# power-control.net
KiCad netlist of a schematic drawn in EAGLE
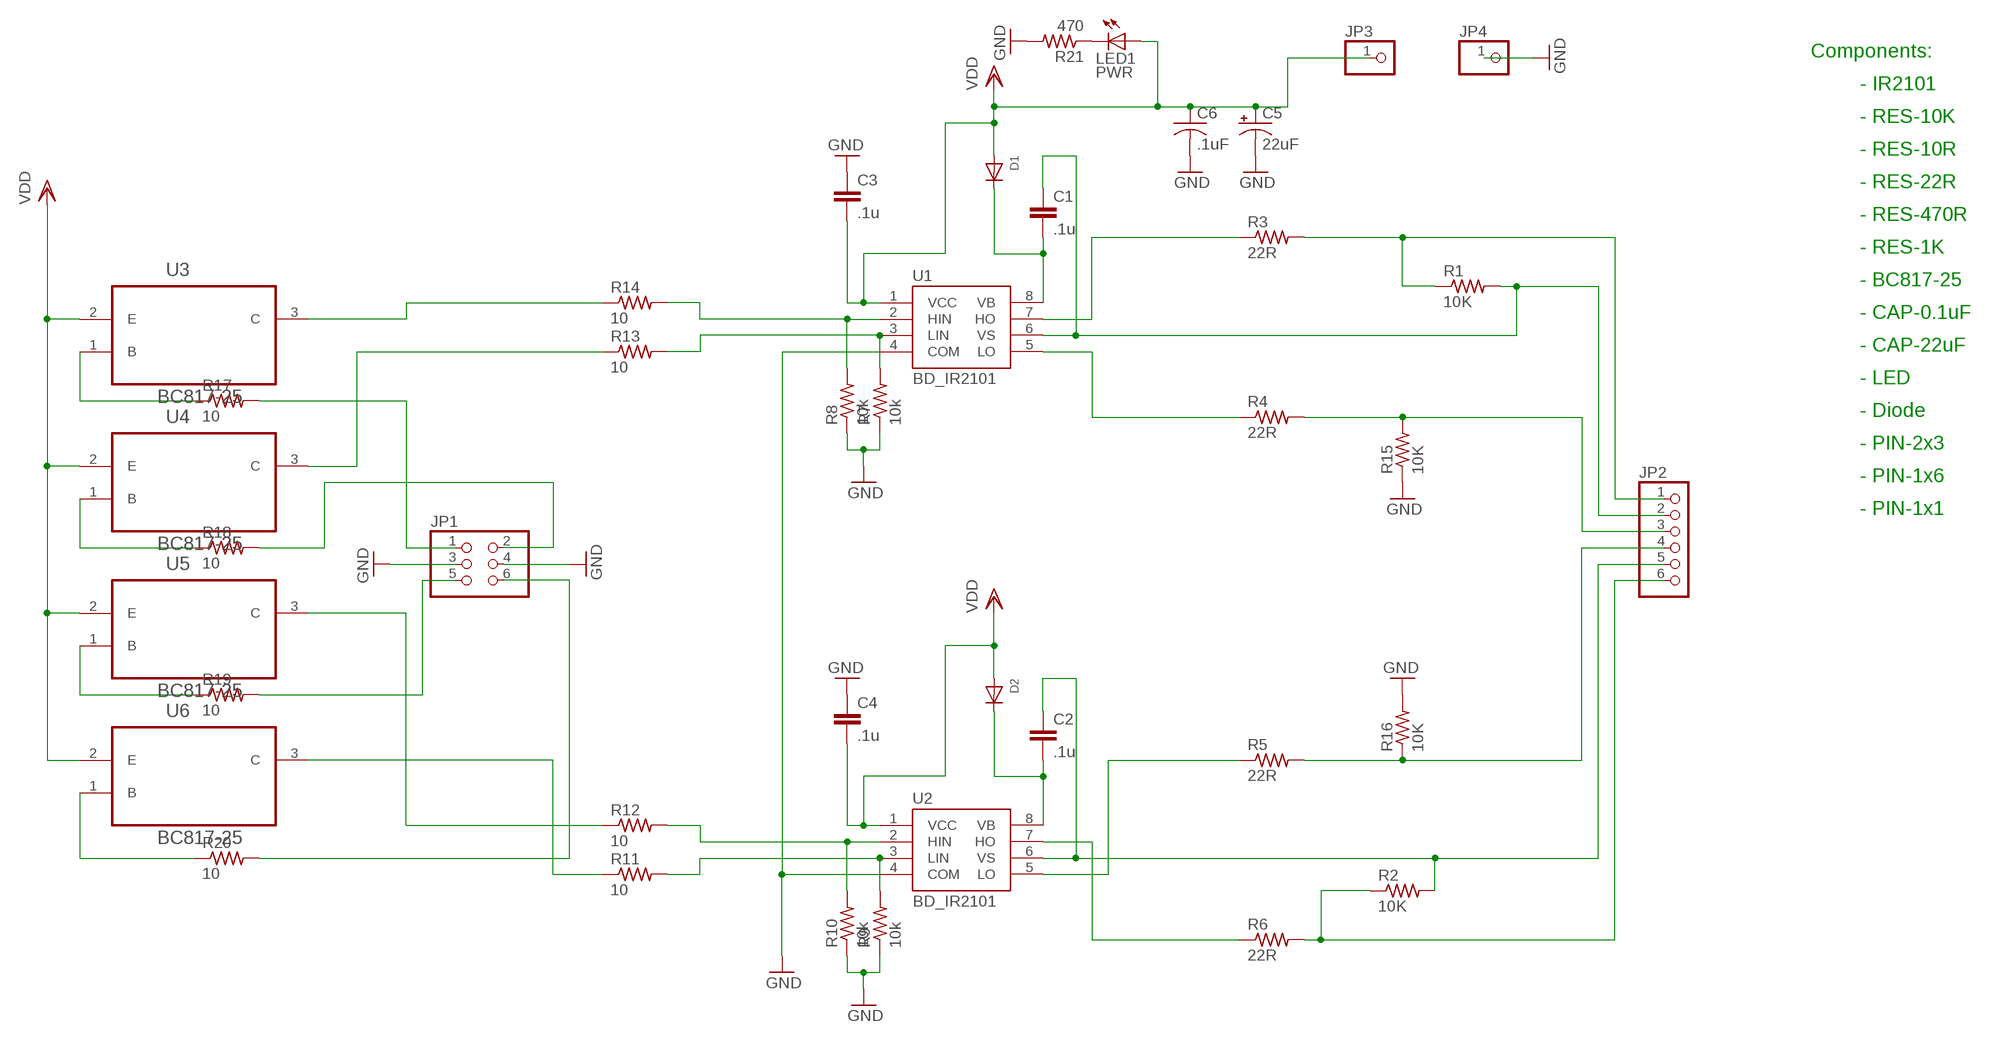
[diagram p0: schematic, sheet 1]

(export (version "E")
  (design (tool "Eeschema 10.0.6"))
  (components
    (comp (ref "C1")
      (value ".1u")
      (footprint "eagle-import:C0603")
      (libsource (lib "eagle-import") (part "C-EUC0603"))
    )
    (comp (ref "C2")
      (value ".1u")
      (footprint "eagle-import:C0603")
      (libsource (lib "eagle-import") (part "C-EUC0603"))
    )
    (comp (ref "C3")
      (value ".1u")
      (footprint "eagle-import:C0603")
      (libsource (lib "eagle-import") (part "C-EUC0603"))
    )
    (comp (ref "C4")
      (value ".1u")
      (footprint "eagle-import:C0603")
      (libsource (lib "eagle-import") (part "C-EUC0603"))
    )
    (comp (ref "C5")
      (value "22uF")
      (footprint "eagle-import:B_3528-21W")
      (libsource (lib "eagle-import") (part "CPOL-USB/3528-21W"))
    )
    (comp (ref "C6")
      (value ".1uF")
      (footprint "eagle-import:C0805")
      (libsource (lib "eagle-import") (part "C-USC0805"))
    )
    (comp (ref "D1")
      (value "DIODESOD-523")
      (footprint "eagle-import:SOD-523")
      (libsource (lib "eagle-import") (part "DIODESOD-523"))
    )
    (comp (ref "D2")
      (value "DIODESOD-523")
      (footprint "eagle-import:SOD-523")
      (libsource (lib "eagle-import") (part "DIODESOD-523"))
    )
    (comp (ref "JP1")
      (value "PINHD-2X3")
      (footprint "eagle-import:2X03")
      (libsource (lib "eagle-import") (part "PINHD-2X3"))
    )
    (comp (ref "JP2")
      (value "PINHD-1X6")
      (footprint "eagle-import:1X06")
      (libsource (lib "eagle-import") (part "PINHD-1X6"))
    )
    (comp (ref "JP3")
      (value "PINHD-1X1")
      (footprint "eagle-import:1X01")
      (libsource (lib "eagle-import") (part "PINHD-1X1"))
    )
    (comp (ref "JP4")
      (value "PINHD-1X1")
      (footprint "eagle-import:1X01")
      (libsource (lib "eagle-import") (part "PINHD-1X1"))
    )
    (comp (ref "LED1")
      (value "PWR")
      (footprint "eagle-import:CHIP-LED0805")
      (libsource (lib "eagle-import") (part "LEDCHIP-LED0805"))
    )
    (comp (ref "R1")
      (value "10K")
      (footprint "eagle-import:R0603")
      (libsource (lib "eagle-import") (part "R-US_R0603"))
    )
    (comp (ref "R2")
      (value "10K")
      (footprint "eagle-import:R0603")
      (libsource (lib "eagle-import") (part "R-US_R0603"))
    )
    (comp (ref "R3")
      (value "22R")
      (footprint "eagle-import:R0603")
      (libsource (lib "eagle-import") (part "R-US_R0603"))
    )
    (comp (ref "R4")
      (value "22R")
      (footprint "eagle-import:R0603")
      (libsource (lib "eagle-import") (part "R-US_R0603"))
    )
    (comp (ref "R5")
      (value "22R")
      (footprint "eagle-import:R0603")
      (libsource (lib "eagle-import") (part "R-US_R0603"))
    )
    (comp (ref "R6")
      (value "22R")
      (footprint "eagle-import:R0603")
      (libsource (lib "eagle-import") (part "R-US_R0603"))
    )
    (comp (ref "R7")
      (value "10k")
      (footprint "eagle-import:R0603")
      (libsource (lib "eagle-import") (part "R-US_R0603"))
    )
    (comp (ref "R8")
      (value "10k")
      (footprint "eagle-import:R0603")
      (libsource (lib "eagle-import") (part "R-US_R0603"))
    )
    (comp (ref "R9")
      (value "10k")
      (footprint "eagle-import:R0603")
      (libsource (lib "eagle-import") (part "R-US_R0603"))
    )
    (comp (ref "R10")
      (value "10k")
      (footprint "eagle-import:R0603")
      (libsource (lib "eagle-import") (part "R-US_R0603"))
    )
    (comp (ref "R11")
      (value "10")
      (footprint "eagle-import:R0603")
      (libsource (lib "eagle-import") (part "R-US_R0603"))
    )
    (comp (ref "R12")
      (value "10")
      (footprint "eagle-import:R0603")
      (libsource (lib "eagle-import") (part "R-US_R0603"))
    )
    (comp (ref "R13")
      (value "10")
      (footprint "eagle-import:R0603")
      (libsource (lib "eagle-import") (part "R-US_R0603"))
    )
    (comp (ref "R14")
      (value "10")
      (footprint "eagle-import:R0603")
      (libsource (lib "eagle-import") (part "R-US_R0603"))
    )
    (comp (ref "R15")
      (value "10K")
      (footprint "eagle-import:R0603")
      (libsource (lib "eagle-import") (part "R-US_R0603"))
    )
    (comp (ref "R16")
      (value "10K")
      (footprint "eagle-import:R0603")
      (libsource (lib "eagle-import") (part "R-US_R0603"))
    )
    (comp (ref "R17")
      (value "10")
      (footprint "eagle-import:R0603")
      (libsource (lib "eagle-import") (part "R-US_R0603"))
    )
    (comp (ref "R18")
      (value "10")
      (footprint "eagle-import:R0603")
      (libsource (lib "eagle-import") (part "R-US_R0603"))
    )
    (comp (ref "R19")
      (value "10")
      (footprint "eagle-import:R0603")
      (libsource (lib "eagle-import") (part "R-US_R0603"))
    )
    (comp (ref "R20")
      (value "10")
      (footprint "eagle-import:R0603")
      (libsource (lib "eagle-import") (part "R-US_R0603"))
    )
    (comp (ref "R21")
      (value "470")
      (footprint "eagle-import:R0603")
      (libsource (lib "eagle-import") (part "R-US_R0603"))
    )
    (comp (ref "U1")
      (value "BD_IR2101")
      (footprint "eagle-import:SO8")
      (libsource (lib "eagle-import") (part "BD_IR2101"))
    )
    (comp (ref "U2")
      (value "BD_IR2101")
      (footprint "eagle-import:SO8")
      (libsource (lib "eagle-import") (part "BD_IR2101"))
    )
    (comp (ref "U3")
      (value "BC817-25")
      (footprint "eagle-import:SOT95P240X97-3N")
      (libsource (lib "eagle-import") (part "BC817-25"))
    )
    (comp (ref "U4")
      (value "BC817-25")
      (footprint "eagle-import:SOT95P240X97-3N")
      (libsource (lib "eagle-import") (part "BC817-25"))
    )
    (comp (ref "U5")
      (value "BC817-25")
      (footprint "eagle-import:SOT95P240X97-3N")
      (libsource (lib "eagle-import") (part "BC817-25"))
    )
    (comp (ref "U6")
      (value "BC817-25")
      (footprint "eagle-import:SOT95P240X97-3N")
      (libsource (lib "eagle-import") (part "BC817-25"))
    )
  )
  (nets
    (net (code "1") (name "GND") (class "Default")
      (node (ref "C3") (pin "1") (pinfunction "1_1") (pintype "passive"))
      (node (ref "C4") (pin "1") (pinfunction "1_1") (pintype "passive"))
      (node (ref "C5") (pin "-") (pinfunction "-_-") (pintype "passive"))
      (node (ref "C6") (pin "2") (pinfunction "2_2") (pintype "passive"))
      (node (ref "JP1") (pin "3") (pinfunction "3_3") (pintype "passive"))
      (node (ref "JP1") (pin "4") (pinfunction "4_4") (pintype "passive"))
      (node (ref "JP4") (pin "1") (pinfunction "1_1") (pintype "passive"))
      (node (ref "R10") (pin "1") (pinfunction "1_1") (pintype "passive"))
      (node (ref "R15") (pin "1") (pinfunction "1_1") (pintype "passive"))
      (node (ref "R16") (pin "2") (pinfunction "2_2") (pintype "passive"))
      (node (ref "R21") (pin "2") (pinfunction "2_2") (pintype "passive"))
      (node (ref "R7") (pin "1") (pinfunction "1_1") (pintype "passive"))
      (node (ref "R8") (pin "1") (pinfunction "1_1") (pintype "passive"))
      (node (ref "R9") (pin "1") (pinfunction "1_1") (pintype "passive"))
      (node (ref "U1") (pin "4") (pinfunction "COM_4") (pintype "bidirectional"))
      (node (ref "U2") (pin "4") (pinfunction "COM_4") (pintype "bidirectional"))
    )
    (net (code "2") (name "Net-(D1-C)") (class "Default")
      (node (ref "C1") (pin "2") (pinfunction "2_2") (pintype "passive"))
      (node (ref "D1") (pin "K") (pinfunction "C_K") (pintype "passive"))
      (node (ref "U1") (pin "8") (pinfunction "VB_8") (pintype "bidirectional"))
    )
    (net (code "3") (name "Net-(D2-C)") (class "Default")
      (node (ref "C2") (pin "2") (pinfunction "2_2") (pintype "passive"))
      (node (ref "D2") (pin "K") (pinfunction "C_K") (pintype "passive"))
      (node (ref "U2") (pin "8") (pinfunction "VB_8") (pintype "bidirectional"))
    )
    (net (code "4") (name "Net-(JP1-Pad1)") (class "Default")
      (node (ref "JP1") (pin "1") (pinfunction "1_1") (pintype "passive"))
      (node (ref "R17") (pin "2") (pinfunction "2_2") (pintype "passive"))
    )
    (net (code "5") (name "Net-(JP1-Pad2)") (class "Default")
      (node (ref "JP1") (pin "2") (pinfunction "2_2") (pintype "passive"))
      (node (ref "R18") (pin "2") (pinfunction "2_2") (pintype "passive"))
    )
    (net (code "6") (name "Net-(JP1-Pad5)") (class "Default")
      (node (ref "JP1") (pin "5") (pinfunction "5_5") (pintype "passive"))
      (node (ref "R19") (pin "2") (pinfunction "2_2") (pintype "passive"))
    )
    (net (code "7") (name "Net-(JP1-Pad6)") (class "Default")
      (node (ref "JP1") (pin "6") (pinfunction "6_6") (pintype "passive"))
      (node (ref "R20") (pin "2") (pinfunction "2_2") (pintype "passive"))
    )
    (net (code "8") (name "Net-(JP2-Pad1)") (class "Default")
      (node (ref "JP2") (pin "1") (pinfunction "1_1") (pintype "passive"))
      (node (ref "R1") (pin "1") (pinfunction "1_1") (pintype "passive"))
      (node (ref "R3") (pin "2") (pinfunction "2_2") (pintype "passive"))
    )
    (net (code "9") (name "Net-(JP2-Pad3)") (class "Default")
      (node (ref "JP2") (pin "3") (pinfunction "3_3") (pintype "passive"))
      (node (ref "R15") (pin "2") (pinfunction "2_2") (pintype "passive"))
      (node (ref "R4") (pin "2") (pinfunction "2_2") (pintype "passive"))
    )
    (net (code "10") (name "Net-(JP2-Pad4)") (class "Default")
      (node (ref "JP2") (pin "4") (pinfunction "4_4") (pintype "passive"))
      (node (ref "R16") (pin "1") (pinfunction "1_1") (pintype "passive"))
      (node (ref "R5") (pin "2") (pinfunction "2_2") (pintype "passive"))
    )
    (net (code "11") (name "Net-(JP2-Pad6)") (class "Default")
      (node (ref "JP2") (pin "6") (pinfunction "6_6") (pintype "passive"))
      (node (ref "R2") (pin "1") (pinfunction "1_1") (pintype "passive"))
      (node (ref "R6") (pin "2") (pinfunction "2_2") (pintype "passive"))
    )
    (net (code "12") (name "Net-(LED1-PadC)") (class "Default")
      (node (ref "LED1") (pin "C") (pinfunction "C_C") (pintype "passive"))
      (node (ref "R21") (pin "1") (pinfunction "1_1") (pintype "passive"))
    )
    (net (code "13") (name "Net-(U1-HIN)") (class "Default")
      (node (ref "R14") (pin "2") (pinfunction "2_2") (pintype "passive"))
      (node (ref "R8") (pin "2") (pinfunction "2_2") (pintype "passive"))
      (node (ref "U1") (pin "2") (pinfunction "HIN_2") (pintype "bidirectional"))
    )
    (net (code "14") (name "Net-(U1-HO)") (class "Default")
      (node (ref "R3") (pin "1") (pinfunction "1_1") (pintype "passive"))
      (node (ref "U1") (pin "7") (pinfunction "HO_7") (pintype "bidirectional"))
    )
    (net (code "15") (name "Net-(U1-LIN)") (class "Default")
      (node (ref "R13") (pin "2") (pinfunction "2_2") (pintype "passive"))
      (node (ref "R7") (pin "2") (pinfunction "2_2") (pintype "passive"))
      (node (ref "U1") (pin "3") (pinfunction "LIN_3") (pintype "bidirectional"))
    )
    (net (code "16") (name "Net-(U1-LO)") (class "Default")
      (node (ref "R4") (pin "1") (pinfunction "1_1") (pintype "passive"))
      (node (ref "U1") (pin "5") (pinfunction "LO_5") (pintype "bidirectional"))
    )
    (net (code "17") (name "Net-(U1-VS)") (class "Default")
      (node (ref "C1") (pin "1") (pinfunction "1_1") (pintype "passive"))
      (node (ref "JP2") (pin "2") (pinfunction "2_2") (pintype "passive"))
      (node (ref "R1") (pin "2") (pinfunction "2_2") (pintype "passive"))
      (node (ref "U1") (pin "6") (pinfunction "VS_6") (pintype "bidirectional"))
    )
    (net (code "18") (name "Net-(U2-HIN)") (class "Default")
      (node (ref "R10") (pin "2") (pinfunction "2_2") (pintype "passive"))
      (node (ref "R12") (pin "2") (pinfunction "2_2") (pintype "passive"))
      (node (ref "U2") (pin "2") (pinfunction "HIN_2") (pintype "bidirectional"))
    )
    (net (code "19") (name "Net-(U2-HO)") (class "Default")
      (node (ref "R6") (pin "1") (pinfunction "1_1") (pintype "passive"))
      (node (ref "U2") (pin "7") (pinfunction "HO_7") (pintype "bidirectional"))
    )
    (net (code "20") (name "Net-(U2-LIN)") (class "Default")
      (node (ref "R11") (pin "2") (pinfunction "2_2") (pintype "passive"))
      (node (ref "R9") (pin "2") (pinfunction "2_2") (pintype "passive"))
      (node (ref "U2") (pin "3") (pinfunction "LIN_3") (pintype "bidirectional"))
    )
    (net (code "21") (name "Net-(U2-LO)") (class "Default")
      (node (ref "R5") (pin "1") (pinfunction "1_1") (pintype "passive"))
      (node (ref "U2") (pin "5") (pinfunction "LO_5") (pintype "bidirectional"))
    )
    (net (code "22") (name "Net-(U2-VS)") (class "Default")
      (node (ref "C2") (pin "1") (pinfunction "1_1") (pintype "passive"))
      (node (ref "JP2") (pin "5") (pinfunction "5_5") (pintype "passive"))
      (node (ref "R2") (pin "2") (pinfunction "2_2") (pintype "passive"))
      (node (ref "U2") (pin "6") (pinfunction "VS_6") (pintype "bidirectional"))
    )
    (net (code "23") (name "Net-(U3-B)") (class "Default")
      (node (ref "R17") (pin "1") (pinfunction "1_1") (pintype "passive"))
      (node (ref "U3") (pin "1") (pinfunction "B_1") (pintype "passive"))
    )
    (net (code "24") (name "Net-(U3-C)") (class "Default")
      (node (ref "R14") (pin "1") (pinfunction "1_1") (pintype "passive"))
      (node (ref "U3") (pin "3") (pinfunction "C_3") (pintype "passive"))
    )
    (net (code "25") (name "Net-(U4-B)") (class "Default")
      (node (ref "R18") (pin "1") (pinfunction "1_1") (pintype "passive"))
      (node (ref "U4") (pin "1") (pinfunction "B_1") (pintype "passive"))
    )
    (net (code "26") (name "Net-(U4-C)") (class "Default")
      (node (ref "R13") (pin "1") (pinfunction "1_1") (pintype "passive"))
      (node (ref "U4") (pin "3") (pinfunction "C_3") (pintype "passive"))
    )
    (net (code "27") (name "Net-(U5-B)") (class "Default")
      (node (ref "R19") (pin "1") (pinfunction "1_1") (pintype "passive"))
      (node (ref "U5") (pin "1") (pinfunction "B_1") (pintype "passive"))
    )
    (net (code "28") (name "Net-(U5-C)") (class "Default")
      (node (ref "R12") (pin "1") (pinfunction "1_1") (pintype "passive"))
      (node (ref "U5") (pin "3") (pinfunction "C_3") (pintype "passive"))
    )
    (net (code "29") (name "Net-(U6-B)") (class "Default")
      (node (ref "R20") (pin "1") (pinfunction "1_1") (pintype "passive"))
      (node (ref "U6") (pin "1") (pinfunction "B_1") (pintype "passive"))
    )
    (net (code "30") (name "Net-(U6-C)") (class "Default")
      (node (ref "R11") (pin "1") (pinfunction "1_1") (pintype "passive"))
      (node (ref "U6") (pin "3") (pinfunction "C_3") (pintype "passive"))
    )
    (net (code "31") (name "VDD") (class "Default")
      (node (ref "C3") (pin "2") (pinfunction "2_2") (pintype "passive"))
      (node (ref "C4") (pin "2") (pinfunction "2_2") (pintype "passive"))
      (node (ref "C5") (pin "+") (pinfunction "+_+") (pintype "passive"))
      (node (ref "C6") (pin "1") (pinfunction "1_1") (pintype "passive"))
      (node (ref "D1") (pin "A") (pinfunction "A_A") (pintype "passive"))
      (node (ref "D2") (pin "A") (pinfunction "A_A") (pintype "passive"))
      (node (ref "JP3") (pin "1") (pinfunction "1_1") (pintype "passive"))
      (node (ref "LED1") (pin "A") (pinfunction "A_A") (pintype "passive"))
      (node (ref "U1") (pin "1") (pinfunction "VCC_1") (pintype "bidirectional"))
      (node (ref "U2") (pin "1") (pinfunction "VCC_1") (pintype "bidirectional"))
      (node (ref "U3") (pin "2") (pinfunction "E_2") (pintype "passive"))
      (node (ref "U4") (pin "2") (pinfunction "E_2") (pintype "passive"))
      (node (ref "U5") (pin "2") (pinfunction "E_2") (pintype "passive"))
      (node (ref "U6") (pin "2") (pinfunction "E_2") (pintype "passive"))
    )
  )
)
